# DEBUG.net
KiCad netlist of a schematic drawn in Altium Designer
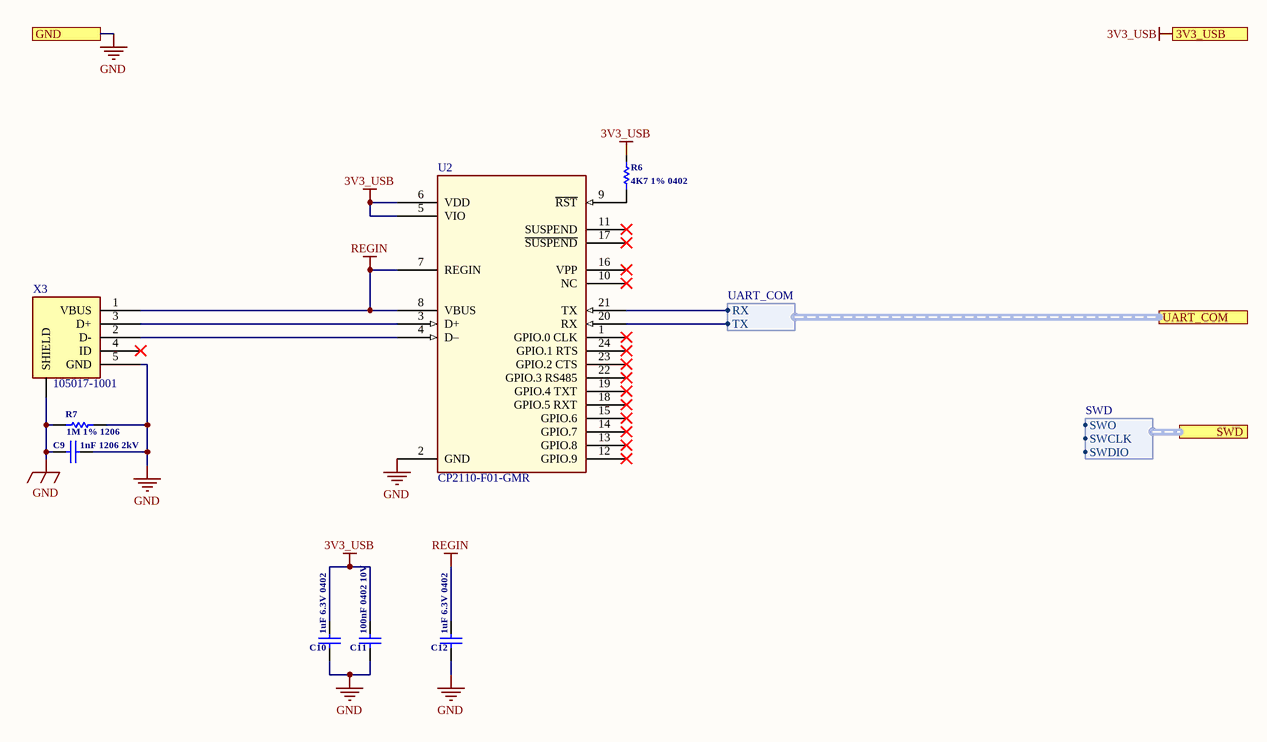
[diagram p0: DEBUG.SchDoc]

(export (version "E")
  (design (tool "Eeschema 10.0.6"))
  (components
    (comp (ref "C9")
      (value "1nF 1206 2kV")
      (libsource (lib "CondensadoresGenericos") (part "CL31B102KJHNNNE 1nF 2kV 1206"))
    )
    (comp (ref "C10")
      (value "1uF 6.3V 0402")
      (fields
        (field (name "MANUFACTURER") "Samsung")
        (field (name "MANUFACTURER PART NUMBER") "CL05A105KQ5NNNC")
      )
      (libsource (lib "CondensadoresGenericos") (part "CL05A105KQ5NNNC 1uF 0402"))
    )
    (comp (ref "C11")
      (value "100nF 0402 10V")
      (description "Cap Ceramic 0.1uF 10V X5R 10% SMD 0402 85C Paper T/R")
      (fields
        (field (name "MANUFACTURER") "Samsung")
        (field (name "MANUFACTURER PART NUMBER") "CL05A104KP5NNNC")
      )
      (libsource (lib "CondensadoresGenericos") (part "CL05A104KP5NNNC 100nF 0402 10V"))
    )
    (comp (ref "C12")
      (value "1uF 6.3V 0402")
      (fields
        (field (name "MANUFACTURER") "Samsung")
        (field (name "MANUFACTURER PART NUMBER") "CL05A105KQ5NNNC")
      )
      (libsource (lib "CondensadoresGenericos") (part "CL05A105KQ5NNNC 1uF 0402"))
    )
    (comp (ref "R6")
      (value "4K7 1% 0402")
      (footprint "Resistor_0402")
      (description "Thick Film Resistors 1/16W 4.7K ohm 1% AEC-Q200")
      (fields
        (field (name "MANUFACTURER") "Yageo")
        (field (name "MANUFACTURER PART NUMBER") "AC0402FR-074K7L")
      )
      (libsource (lib "ResistenciasGenericas") (part "AC0402FR-074K7L 4.7K 1% 0402"))
    )
    (comp (ref "R7")
      (value "1M 1% 1206")
      (libsource (lib "ResistenciasGenericas") (part "RMCF1206FT1M00 1M 1% 1206"))
    )
    (comp (ref "U2")
      (value "CP2110-F01-GMR")
      (description "IC HID USB-TO-UART BRIDGE 24QFN")
      (fields (field (name "MANUFACTURER") "Silicon Labs"))
      (libsource (lib "USB_uart_conversor") (part "CP2110-F01-GMR"))
    )
    (comp (ref "X3")
      (value "105017-1001")
      (footprint "1050170001")
      (libsource (lib "Connectors") (part "microUSB_105017-1001"))
    )
  )
  (nets
    (net (code "3") (name "/RX") (class "Default")
      (node (ref "U2") (pin "21") (pinfunction "TX_21") (pintype "input"))
    )
    (net (code "4") (name "/TX") (class "Default")
      (node (ref "U2") (pin "20") (pinfunction "RX_20") (pintype "input"))
    )
    (net (code "7") (name "3V3_USB") (class "Default")
      (node (ref "C10") (pin "2") (pinfunction "2_2") (pintype "passive"))
      (node (ref "C11") (pin "2") (pinfunction "2_2") (pintype "passive"))
      (node (ref "U2") (pin "5") (pinfunction "VIO_5") (pintype "power_in"))
      (node (ref "U2") (pin "6") (pinfunction "VDD_6") (pintype "power_in"))
    )
    (net (code "8") (name "GND") (class "Default")
      (node (ref "C10") (pin "1") (pinfunction "1_1") (pintype "passive"))
      (node (ref "C11") (pin "1") (pinfunction "1_1") (pintype "passive"))
      (node (ref "C12") (pin "1") (pinfunction "1_1") (pintype "passive"))
      (node (ref "C9") (pin "1") (pinfunction "1_1") (pintype "passive"))
      (node (ref "C9") (pin "2") (pinfunction "2_2") (pintype "passive"))
      (node (ref "R7") (pin "1") (pinfunction "1_1") (pintype "passive"))
      (node (ref "R7") (pin "2") (pinfunction "2_2") (pintype "passive"))
      (node (ref "U2") (pin "2") (pinfunction "GND_2") (pintype "power_in"))
      (node (ref "X3") (pin "5") (pinfunction "GND_5") (pintype "passive"))
      (node (ref "X3") (pin "SH1") (pinfunction "SHIELD_SH1") (pintype "passive"))
    )
    (net (code "9") (name "Net-(U2-D+)") (class "Default")
      (node (ref "U2") (pin "3") (pinfunction "D+_3") (pintype "input"))
      (node (ref "X3") (pin "3") (pinfunction "D+_3") (pintype "passive"))
    )
    (net (code "10") (name "Net-(U2-D–)") (class "Default")
      (node (ref "U2") (pin "4") (pinfunction "D–_4") (pintype "input"))
      (node (ref "X3") (pin "2") (pinfunction "D-_2") (pintype "passive"))
    )
    (net (code "11") (name "Net-(U2-~{RST})") (class "Default")
      (node (ref "R6") (pin "1") (pinfunction "1_1") (pintype "passive"))
      (node (ref "U2") (pin "9") (pinfunction "~{RST}_9") (pintype "input"))
    )
    (net (code "12") (name "REGIN") (class "Default")
      (node (ref "C12") (pin "2") (pinfunction "2_2") (pintype "passive"))
      (node (ref "U2") (pin "7") (pinfunction "REGIN_7") (pintype "power_in"))
      (node (ref "U2") (pin "8") (pinfunction "VBUS_8") (pintype "power_in"))
      (node (ref "X3") (pin "1") (pinfunction "VBUS_1") (pintype "passive"))
    )
    (net (code "13") (name "unconnected-(R6-Pad2)") (class "Default")
      (node (ref "R6") (pin "2") (pinfunction "2_2") (pintype "passive"))
    )
    (net (code "14") (name "unconnected-(U2-GPIO.0_CLK-Pad1)") (class "Default")
      (node (ref "U2") (pin "1") (pinfunction "GPIO.0_CLK_1") (pintype "passive+no_connect"))
    )
    (net (code "15") (name "unconnected-(U2-GPIO.1_RTS-Pad24)") (class "Default")
      (node (ref "U2") (pin "24") (pinfunction "GPIO.1_RTS_24") (pintype "passive+no_connect"))
    )
    (net (code "16") (name "unconnected-(U2-GPIO.2_CTS-Pad23)") (class "Default")
      (node (ref "U2") (pin "23") (pinfunction "GPIO.2_CTS_23") (pintype "passive+no_connect"))
    )
    (net (code "17") (name "unconnected-(U2-GPIO.3_RS485-Pad22)") (class "Default")
      (node (ref "U2") (pin "22") (pinfunction "GPIO.3_RS485_22") (pintype "passive+no_connect"))
    )
    (net (code "18") (name "unconnected-(U2-GPIO.4_TXT-Pad19)") (class "Default")
      (node (ref "U2") (pin "19") (pinfunction "GPIO.4_TXT_19") (pintype "passive+no_connect"))
    )
    (net (code "19") (name "unconnected-(U2-GPIO.5_RXT-Pad18)") (class "Default")
      (node (ref "U2") (pin "18") (pinfunction "GPIO.5_RXT_18") (pintype "passive+no_connect"))
    )
    (net (code "20") (name "unconnected-(U2-GPIO.6-Pad15)") (class "Default")
      (node (ref "U2") (pin "15") (pinfunction "GPIO.6_15") (pintype "passive+no_connect"))
    )
    (net (code "21") (name "unconnected-(U2-GPIO.7-Pad14)") (class "Default")
      (node (ref "U2") (pin "14") (pinfunction "GPIO.7_14") (pintype "passive+no_connect"))
    )
    (net (code "22") (name "unconnected-(U2-GPIO.8-Pad13)") (class "Default")
      (node (ref "U2") (pin "13") (pinfunction "GPIO.8_13") (pintype "passive+no_connect"))
    )
    (net (code "23") (name "unconnected-(U2-GPIO.9-Pad12)") (class "Default")
      (node (ref "U2") (pin "12") (pinfunction "GPIO.9_12") (pintype "passive+no_connect"))
    )
    (net (code "24") (name "unconnected-(U2-NC-Pad10)") (class "Default")
      (node (ref "U2") (pin "10") (pinfunction "NC_10") (pintype "passive+no_connect"))
    )
    (net (code "25") (name "unconnected-(U2-SUSPEND-Pad11)") (class "Default")
      (node (ref "U2") (pin "11") (pinfunction "SUSPEND_11") (pintype "passive+no_connect"))
    )
    (net (code "26") (name "unconnected-(U2-VPP-Pad16)") (class "Default")
      (node (ref "U2") (pin "16") (pinfunction "VPP_16") (pintype "passive+no_connect"))
    )
    (net (code "27") (name "unconnected-(U2-~{SUSPEND}-Pad17)") (class "Default")
      (node (ref "U2") (pin "17") (pinfunction "~{SUSPEND}_17") (pintype "passive+no_connect"))
    )
    (net (code "28") (name "unconnected-(X3-ID-Pad4)") (class "Default")
      (node (ref "X3") (pin "4") (pinfunction "ID_4") (pintype "passive+no_connect"))
    )
  )
)
